# BH1750.net
KiCad netlist of a schematic drawn in EasyEDA Pro
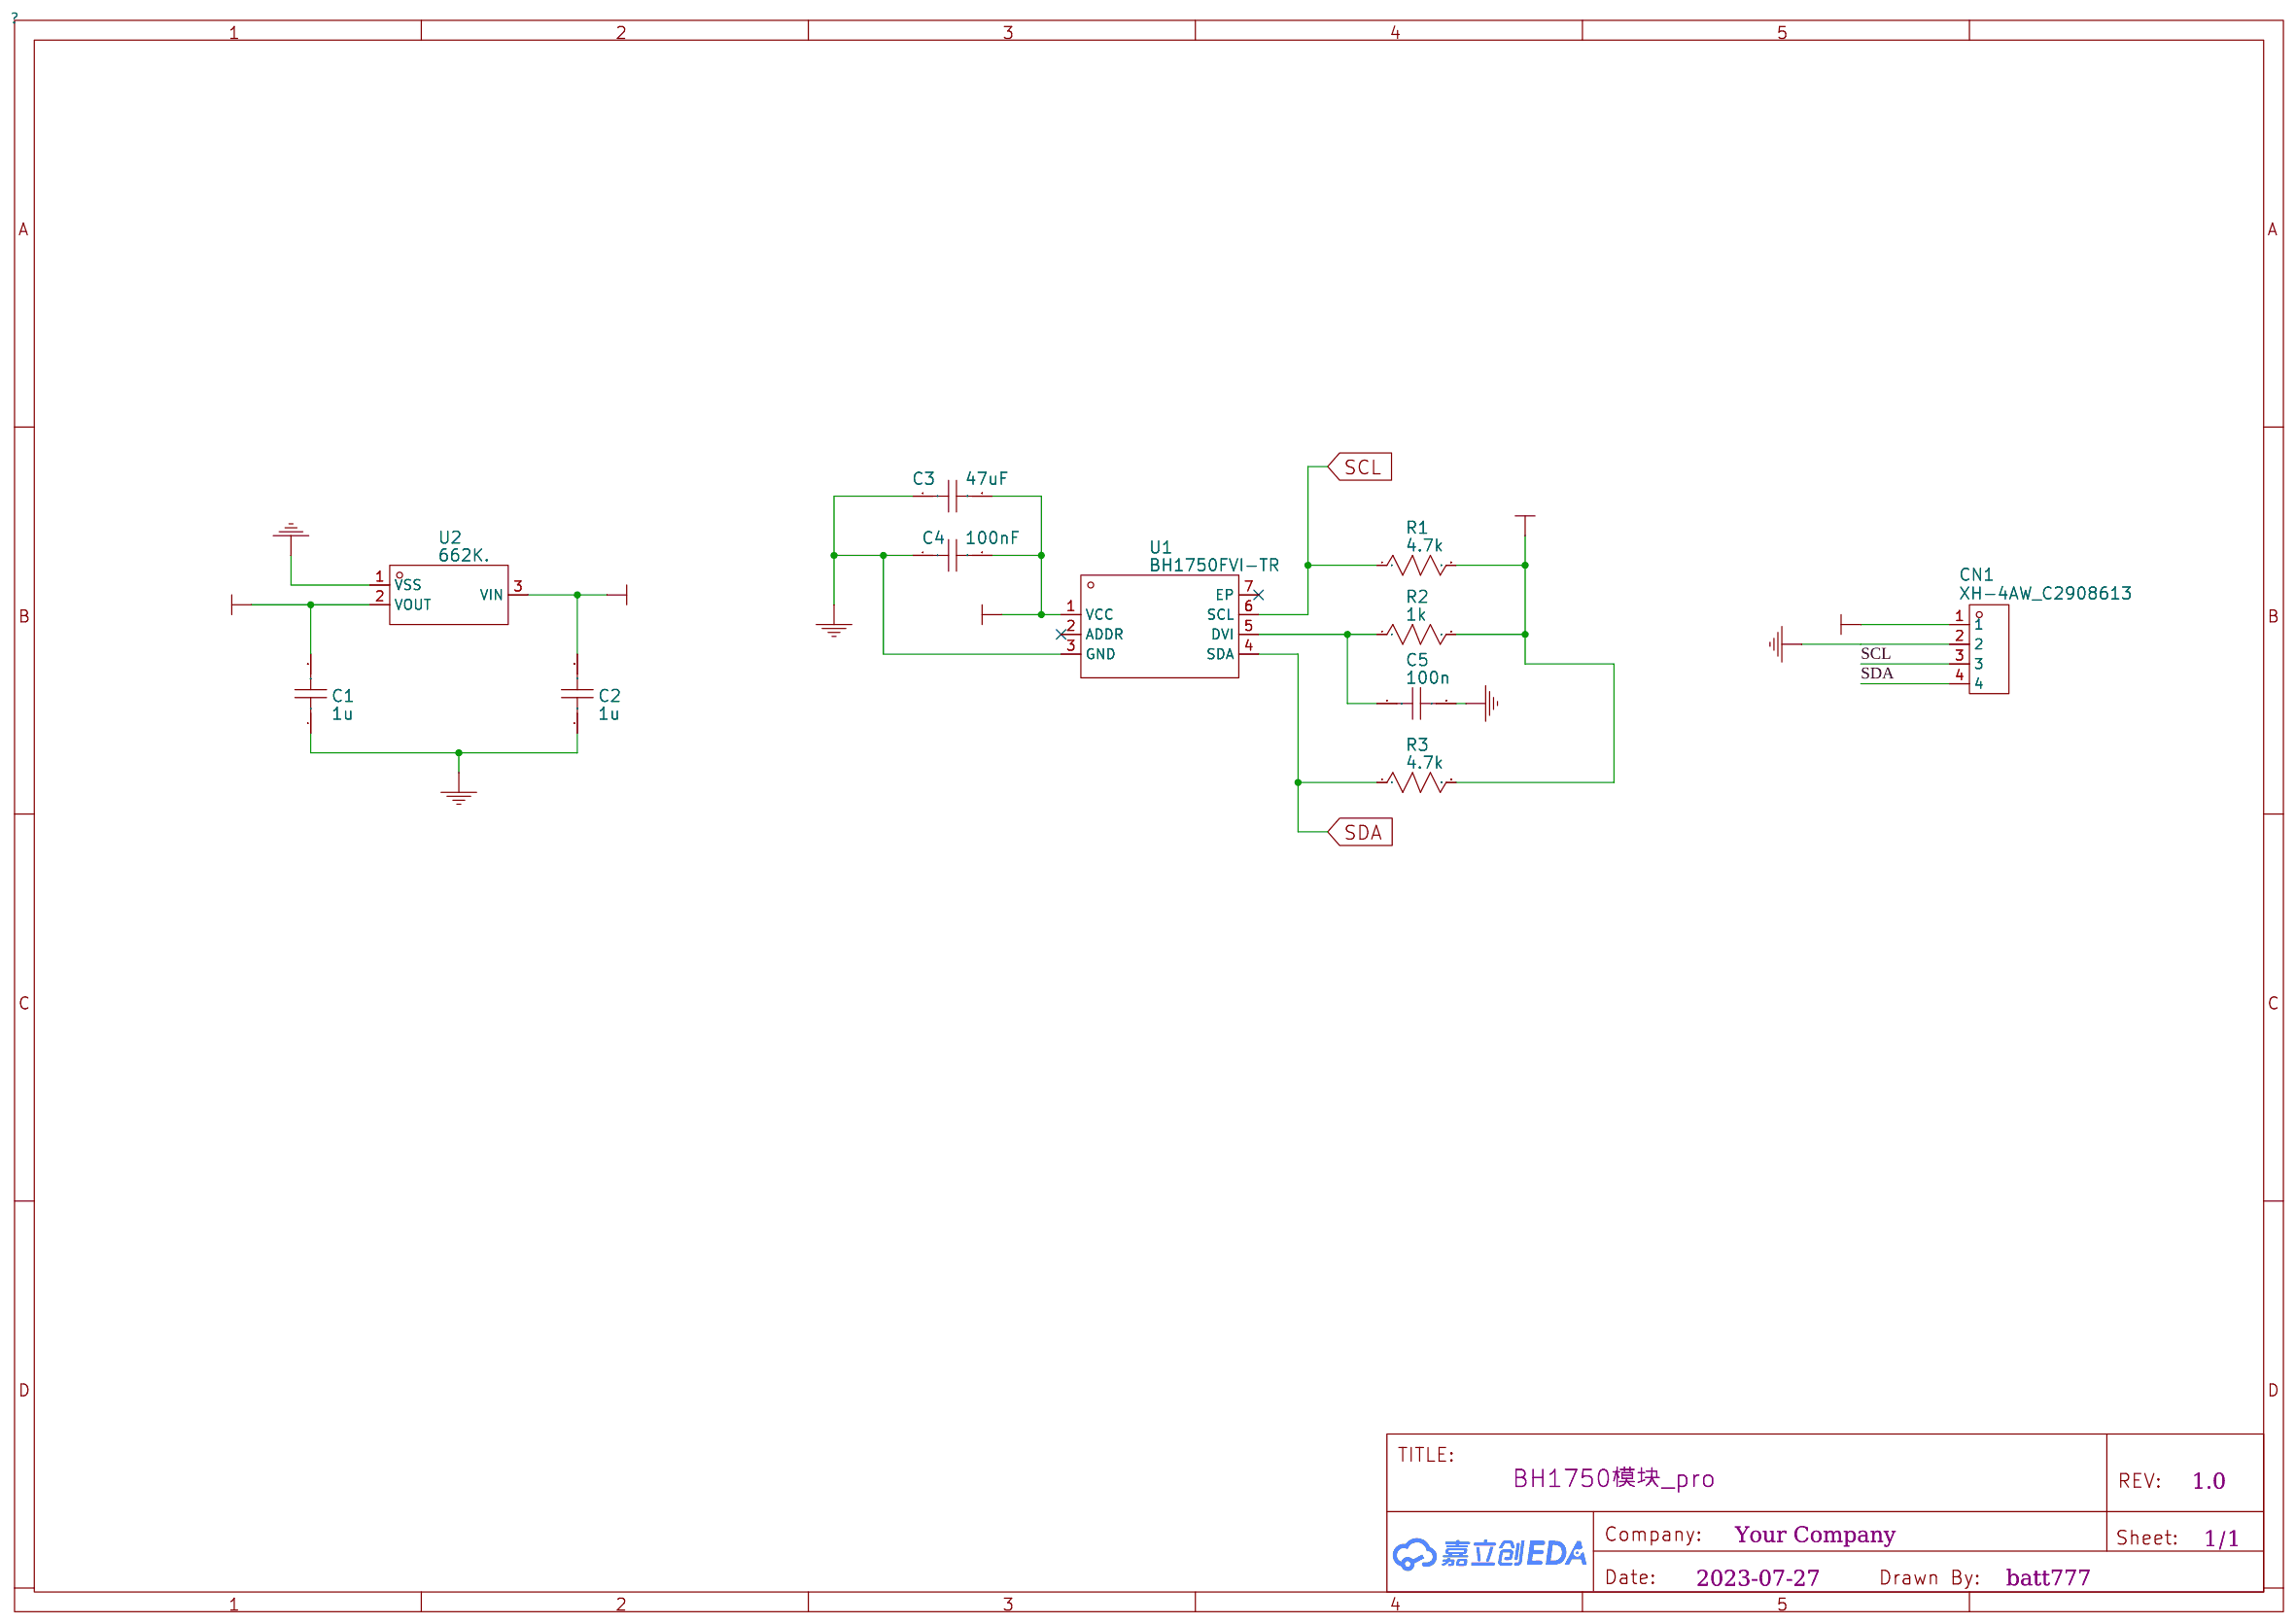
[diagram p0: schematic sheet]

(export (version "E")
  (design (tool "Eeschema 10.0.6"))
  (components
    (comp (ref "C1") (value "1u") (footprint "easyedapro:C0603") (libsource (lib "easyedapro") (part "1u")))
    (comp (ref "C2") (value "1u") (footprint "easyedapro:C0603") (libsource (lib "easyedapro") (part "1u")))
    (comp (ref "C3")
      (value "47uF")
      (footprint "easyedapro:C0603")
      (libsource (lib "easyedapro") (part "47uF"))
    )
    (comp (ref "C4")
      (value "100nF")
      (footprint "easyedapro:C0603")
      (libsource (lib "easyedapro") (part "100nF"))
    )
    (comp (ref "C5")
      (value "100n")
      (footprint "easyedapro:C0603")
      (libsource (lib "easyedapro") (part "100n"))
    )
    (comp (ref "CN1")
      (value "XH-4AW_C2908613")
      (footprint "easyedapro:CONN-TH_XH-4AW")
      (fields (field (name "Manufacturer Part") "XH-4AW") (field (name "Manufacturer") "HCTL(华灿天禄)"))
      (libsource (lib "easyedapro") (part "XH-4AW_C2908613"))
    )
    (comp (ref "R1")
      (value "4.7k")
      (footprint "easyedapro:R0603")
      (libsource (lib "easyedapro") (part "4.7k"))
    )
    (comp (ref "R2") (value "1k") (footprint "easyedapro:R0603") (libsource (lib "easyedapro") (part "1k")))
    (comp (ref "R3")
      (value "4.7k")
      (footprint "easyedapro:R0603")
      (libsource (lib "easyedapro") (part "4.7k"))
    )
    (comp (ref "U1")
      (value "BH1750FVI-TR")
      (footprint "easyedapro:WSOF-6_L2.6-W1.6-P0.50-TL-EP")
      (fields (field (name "Manufacturer") "ROHM(罗姆)"))
      (libsource (lib "easyedapro") (part "BH1750FVI-TR"))
    )
    (comp (ref "U2")
      (value "662K.")
      (footprint "easyedapro:SOT-23-3_L2.9-W1.3-P1.90-LS2.4-BR")
      (fields (field (name "Manufacturer") "FM(富满)"))
      (libsource (lib "easyedapro") (part "662K."))
    )
  )
  (nets
    (net (code "1") (name "+5V") (class "Default")
      (node (ref "C2") (pin "2") (pinfunction "2_2") (pintype "input"))
      (node (ref "CN1") (pin "1") (pinfunction "1_1") (pintype "input"))
      (node (ref "U2") (pin "3") (pinfunction "VIN_3") (pintype "input"))
    )
    (net (code "2") (name "3V3") (class "Default")
      (node (ref "C1") (pin "2") (pinfunction "2_2") (pintype "input"))
      (node (ref "C3") (pin "2") (pinfunction "2_2") (pintype "input"))
      (node (ref "C4") (pin "2") (pinfunction "2_2") (pintype "input"))
      (node (ref "R1") (pin "2") (pinfunction "2_2") (pintype "input"))
      (node (ref "R2") (pin "2") (pinfunction "2_2") (pintype "input"))
      (node (ref "R3") (pin "2") (pinfunction "2_2") (pintype "input"))
      (node (ref "U1") (pin "1") (pinfunction "VCC_1") (pintype "input"))
      (node (ref "U2") (pin "2") (pinfunction "VOUT_2") (pintype "input"))
    )
    (net (code "3") (name "GND") (class "Default")
      (node (ref "C1") (pin "1") (pinfunction "1_1") (pintype "input"))
      (node (ref "C2") (pin "1") (pinfunction "1_1") (pintype "input"))
      (node (ref "C3") (pin "1") (pinfunction "1_1") (pintype "input"))
      (node (ref "C4") (pin "1") (pinfunction "1_1") (pintype "input"))
      (node (ref "C5") (pin "2") (pinfunction "2_2") (pintype "input"))
      (node (ref "CN1") (pin "2") (pinfunction "2_2") (pintype "input"))
      (node (ref "U1") (pin "3") (pinfunction "GND_3") (pintype "input"))
      (node (ref "U2") (pin "1") (pinfunction "VSS_1") (pintype "input"))
    )
    (net (code "4") (name "Net-(U1-DVI)") (class "Default")
      (node (ref "C5") (pin "1") (pinfunction "1_1") (pintype "input"))
      (node (ref "R2") (pin "1") (pinfunction "1_1") (pintype "input"))
      (node (ref "U1") (pin "5") (pinfunction "DVI_5") (pintype "input"))
    )
    (net (code "5") (name "SCL") (class "Default")
      (node (ref "CN1") (pin "3") (pinfunction "3_3") (pintype "input"))
      (node (ref "R1") (pin "1") (pinfunction "1_1") (pintype "input"))
      (node (ref "U1") (pin "6") (pinfunction "SCL_6") (pintype "input"))
    )
    (net (code "6") (name "SDA") (class "Default")
      (node (ref "CN1") (pin "4") (pinfunction "4_4") (pintype "input"))
      (node (ref "R3") (pin "1") (pinfunction "1_1") (pintype "input"))
      (node (ref "U1") (pin "4") (pinfunction "SDA_4") (pintype "input"))
    )
    (net (code "7") (name "unconnected-(U1-ADDR-Pad2)") (class "Default")
      (node (ref "U1") (pin "2") (pinfunction "ADDR_2") (pintype "input+no_connect"))
    )
    (net (code "8") (name "unconnected-(U1-EP-Pad7)") (class "Default")
      (node (ref "U1") (pin "7") (pinfunction "EP_7") (pintype "input+no_connect"))
    )
  )
)
